# ACSN_v1.net
KiCad netlist of a schematic drawn in EAGLE
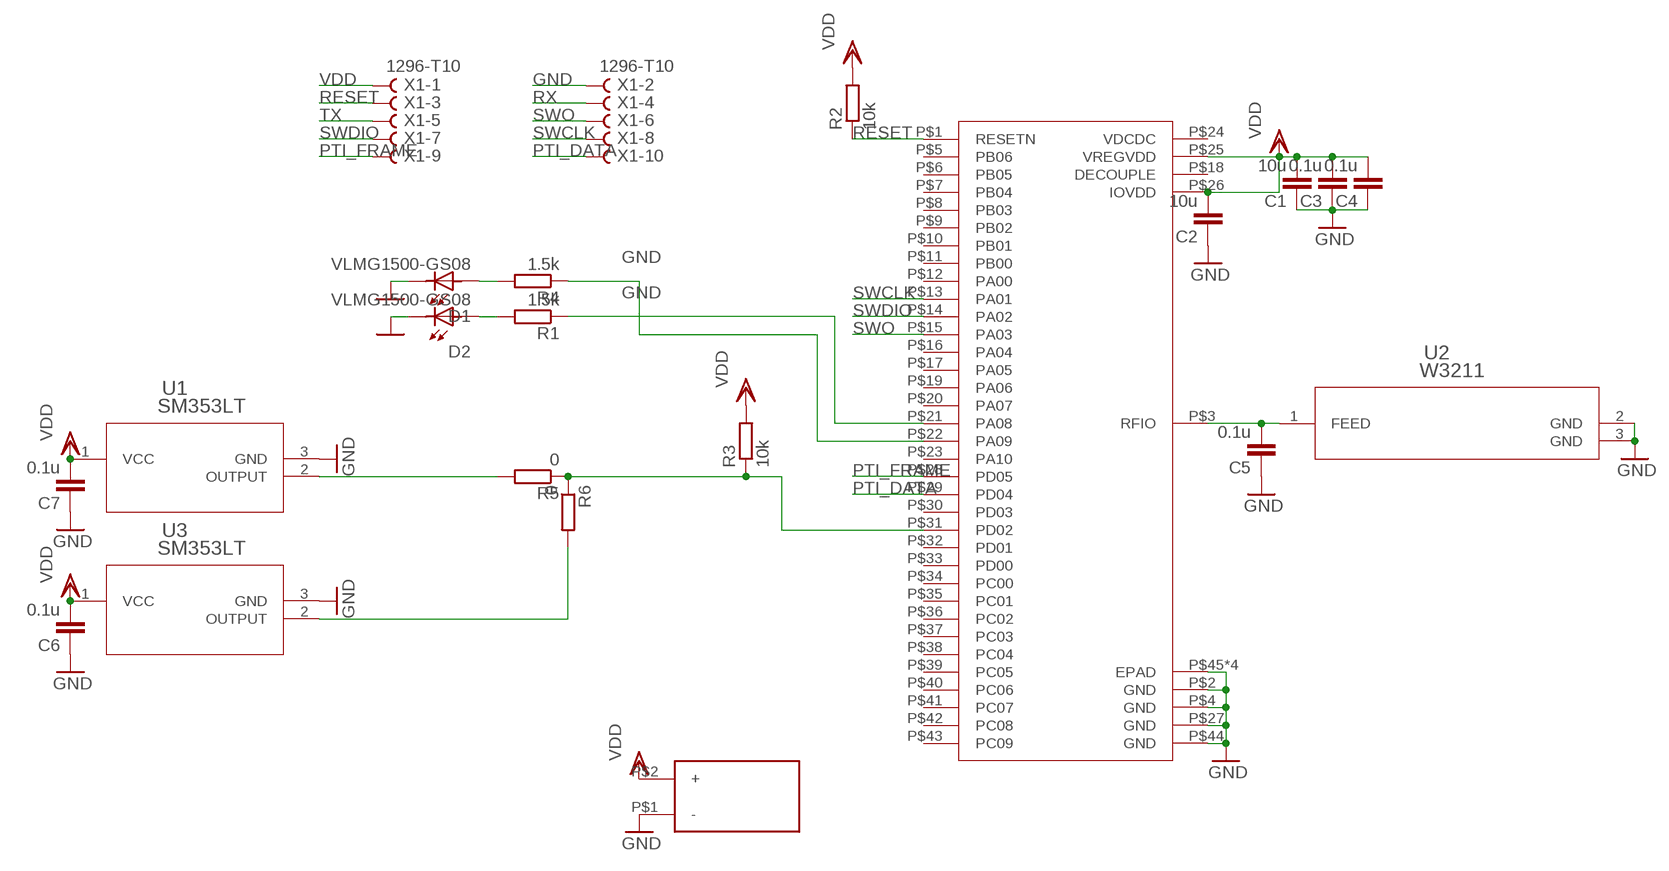
[diagram p0: schematic, sheet 1]

(export (version "E")
  (design (tool "Eeschema 10.0.6"))
  (components
    (comp (ref "C1")
      (value "10u")
      (footprint "eagle-import:C0603R")
      (libsource (lib "eagle-import") (part "CC0603R"))
    )
    (comp (ref "C2")
      (value "10u")
      (footprint "eagle-import:C0603R")
      (libsource (lib "eagle-import") (part "CC0603R"))
    )
    (comp (ref "C3")
      (value "0.1u")
      (footprint "eagle-import:C0402")
      (libsource (lib "eagle-import") (part "CC0402"))
    )
    (comp (ref "C4")
      (value "0.1u")
      (footprint "eagle-import:C0402")
      (libsource (lib "eagle-import") (part "CC0402"))
    )
    (comp (ref "C5")
      (value "0.1u")
      (footprint "eagle-import:C0402")
      (libsource (lib "eagle-import") (part "CC0402"))
    )
    (comp (ref "C6")
      (value "0.1u")
      (footprint "eagle-import:C0402")
      (libsource (lib "eagle-import") (part "CC0402"))
    )
    (comp (ref "C7")
      (value "0.1u")
      (footprint "eagle-import:C0402")
      (libsource (lib "eagle-import") (part "CC0402"))
    )
    (comp (ref "D1")
      (value "VLMG1500-GS08")
      (footprint "eagle-import:LEDC1005X35N")
      (fields (field (name "MF") "Vishay"))
      (libsource (lib "eagle-import") (part "VLMG1500-GS08"))
    )
    (comp (ref "D2")
      (value "VLMG1500-GS08")
      (footprint "eagle-import:LEDC1005X35N")
      (fields (field (name "MF") "Vishay"))
      (libsource (lib "eagle-import") (part "VLMG1500-GS08"))
    )
    (comp (ref "R1")
      (value "1.5k")
      (footprint "eagle-import:R0402")
      (libsource (lib "eagle-import") (part "RR0402"))
    )
    (comp (ref "R2")
      (value "10k")
      (footprint "eagle-import:R0402")
      (libsource (lib "eagle-import") (part "RR0402"))
    )
    (comp (ref "R3")
      (value "10k")
      (footprint "eagle-import:R0402")
      (libsource (lib "eagle-import") (part "RR0402"))
    )
    (comp (ref "R4")
      (value "1.5k")
      (footprint "eagle-import:R0402")
      (libsource (lib "eagle-import") (part "RR0402"))
    )
    (comp (ref "R5")
      (value "0")
      (footprint "eagle-import:R0402")
      (libsource (lib "eagle-import") (part "RR0402"))
    )
    (comp (ref "R6")
      (value "0")
      (footprint "eagle-import:R0402")
      (libsource (lib "eagle-import") (part "RR0402"))
    )
    (comp (ref "U$1")
      (value "ZGM230S")
      (footprint "eagle-import:ZGM230S")
      (libsource (lib "eagle-import") (part "ZGM230S"))
    )
    (comp (ref "U$2")
      (value "BS-24R")
      (footprint "eagle-import:BS-24")
      (libsource (lib "eagle-import") (part "BS-24R"))
    )
    (comp (ref "U1")
      (value "SM353LT")
      (footprint "eagle-import:SM353LT_HNW")
      (fields (field (name "COPYRIGHT") "Copyright (C) 2022 Ultra Librarian. All rights reserved."))
      (libsource (lib "eagle-import") (part "SM353LT"))
    )
    (comp (ref "U2")
      (value "W3211")
      (footprint "eagle-import:CHIP_3211_PUL")
      (fields (field (name "COPYRIGHT") "Copyright (C) 2022 Ultra Librarian. All rights reserved."))
      (libsource (lib "eagle-import") (part "W3211"))
    )
    (comp (ref "U3")
      (value "SM353LT")
      (footprint "eagle-import:SM353LT_HNW")
      (fields (field (name "COPYRIGHT") "Copyright (C) 2022 Ultra Librarian. All rights reserved."))
      (libsource (lib "eagle-import") (part "SM353LT"))
    )
    (comp (ref "X1")
      (value "1296-T10")
      (footprint "eagle-import:1296-10")
      (libsource (lib "eagle-import") (part "1296-T10"))
    )
  )
  (nets
    (net (code "1") (name "/PTI_DATA") (class "Default")
      (node (ref "U$1") (pin "P$29") (pinfunction "PD04_P$29") (pintype "bidirectional"))
      (node (ref "X1") (pin "10") (pinfunction "B_10") (pintype "passive"))
    )
    (net (code "2") (name "/PTI_FRAME") (class "Default")
      (node (ref "U$1") (pin "P$28") (pinfunction "PD05_P$28") (pintype "bidirectional"))
      (node (ref "X1") (pin "9") (pinfunction "B_9") (pintype "passive"))
    )
    (net (code "3") (name "/RESET") (class "Default")
      (node (ref "R2") (pin "1") (pinfunction "1_1") (pintype "passive"))
      (node (ref "U$1") (pin "P$1") (pinfunction "RESETN_P$1") (pintype "bidirectional"))
      (node (ref "X1") (pin "3") (pinfunction "B_3") (pintype "passive"))
    )
    (net (code "4") (name "/RX") (class "Default")
      (node (ref "X1") (pin "4") (pinfunction "B_4") (pintype "passive"))
    )
    (net (code "5") (name "/SWCLK") (class "Default")
      (node (ref "U$1") (pin "P$13") (pinfunction "PA01_P$13") (pintype "bidirectional"))
      (node (ref "X1") (pin "8") (pinfunction "B_8") (pintype "passive"))
    )
    (net (code "6") (name "/SWDIO") (class "Default")
      (node (ref "U$1") (pin "P$14") (pinfunction "PA02_P$14") (pintype "bidirectional"))
      (node (ref "X1") (pin "7") (pinfunction "B_7") (pintype "passive"))
    )
    (net (code "7") (name "/SWO") (class "Default")
      (node (ref "U$1") (pin "P$15") (pinfunction "PA03_P$15") (pintype "bidirectional"))
      (node (ref "X1") (pin "6") (pinfunction "B_6") (pintype "passive"))
    )
    (net (code "8") (name "/TX") (class "Default")
      (node (ref "X1") (pin "5") (pinfunction "B_5") (pintype "passive"))
    )
    (net (code "9") (name "GND") (class "Default")
      (node (ref "C1") (pin "1") (pinfunction "1_1") (pintype "passive"))
      (node (ref "C2") (pin "1") (pinfunction "1_1") (pintype "passive"))
      (node (ref "C3") (pin "1") (pinfunction "1_1") (pintype "passive"))
      (node (ref "C4") (pin "1") (pinfunction "1_1") (pintype "passive"))
      (node (ref "C5") (pin "1") (pinfunction "1_1") (pintype "passive"))
      (node (ref "C6") (pin "1") (pinfunction "1_1") (pintype "passive"))
      (node (ref "C7") (pin "1") (pinfunction "1_1") (pintype "passive"))
      (node (ref "D1") (pin "2") (pinfunction "2_2") (pintype "passive"))
      (node (ref "D2") (pin "2") (pinfunction "2_2") (pintype "passive"))
      (node (ref "U$1") (pin "P$2") (pinfunction "GND_P$2") (pintype "bidirectional"))
      (node (ref "U$1") (pin "P$27") (pinfunction "GND_P$27") (pintype "bidirectional"))
      (node (ref "U$1") (pin "P$4") (pinfunction "GND_P$4") (pintype "bidirectional"))
      (node (ref "U$1") (pin "P$44") (pinfunction "GND_P$44") (pintype "bidirectional"))
      (node (ref "U$1") (pin "P$45") (pinfunction "EPAD_P$45") (pintype "bidirectional"))
      (node (ref "U$1") (pin "P$46") (pinfunction "EPAD_P$46") (pintype "bidirectional"))
      (node (ref "U$1") (pin "P$47") (pinfunction "EPAD_P$47") (pintype "bidirectional"))
      (node (ref "U$1") (pin "P$48") (pinfunction "EPAD_P$48") (pintype "bidirectional"))
      (node (ref "U$2") (pin "P$1") (pinfunction "-_P$1") (pintype "bidirectional"))
      (node (ref "U1") (pin "3") (pinfunction "GND_3") (pintype "passive"))
      (node (ref "U2") (pin "2") (pinfunction "GND_2") (pintype "passive"))
      (node (ref "U2") (pin "3") (pinfunction "GND_3") (pintype "passive"))
      (node (ref "U3") (pin "3") (pinfunction "GND_3") (pintype "passive"))
      (node (ref "X1") (pin "2") (pinfunction "B_2") (pintype "passive"))
    )
    (net (code "10") (name "Net-(D1-Pad1)") (class "Default")
      (node (ref "D1") (pin "1") (pinfunction "1_1") (pintype "passive"))
      (node (ref "R4") (pin "2") (pinfunction "2_2") (pintype "passive"))
    )
    (net (code "11") (name "Net-(D2-Pad1)") (class "Default")
      (node (ref "D2") (pin "1") (pinfunction "1_1") (pintype "passive"))
      (node (ref "R1") (pin "2") (pinfunction "2_2") (pintype "passive"))
    )
    (net (code "12") (name "Net-(U$1-PA08)") (class "Default")
      (node (ref "R1") (pin "1") (pinfunction "1_1") (pintype "passive"))
      (node (ref "U$1") (pin "P$21") (pinfunction "PA08_P$21") (pintype "bidirectional"))
    )
    (net (code "13") (name "Net-(U$1-PA09)") (class "Default")
      (node (ref "R4") (pin "1") (pinfunction "1_1") (pintype "passive"))
      (node (ref "U$1") (pin "P$22") (pinfunction "PA09_P$22") (pintype "bidirectional"))
    )
    (net (code "14") (name "Net-(U$1-PD02)") (class "Default")
      (node (ref "R3") (pin "1") (pinfunction "1_1") (pintype "passive"))
      (node (ref "R5") (pin "1") (pinfunction "1_1") (pintype "passive"))
      (node (ref "R6") (pin "1") (pinfunction "1_1") (pintype "passive"))
      (node (ref "U$1") (pin "P$31") (pinfunction "PD02_P$31") (pintype "bidirectional"))
    )
    (net (code "15") (name "Net-(U$1-RFIO)") (class "Default")
      (node (ref "C5") (pin "2") (pinfunction "2_2") (pintype "passive"))
      (node (ref "U$1") (pin "P$3") (pinfunction "RFIO_P$3") (pintype "bidirectional"))
      (node (ref "U2") (pin "1") (pinfunction "FEED_1") (pintype "passive"))
    )
    (net (code "16") (name "Net-(U1-OUTPUT)") (class "Default")
      (node (ref "R5") (pin "2") (pinfunction "2_2") (pintype "passive"))
      (node (ref "U1") (pin "2") (pinfunction "OUTPUT_2") (pintype "output"))
    )
    (net (code "17") (name "Net-(U3-OUTPUT)") (class "Default")
      (node (ref "R6") (pin "2") (pinfunction "2_2") (pintype "passive"))
      (node (ref "U3") (pin "2") (pinfunction "OUTPUT_2") (pintype "output"))
    )
    (net (code "18") (name "VDD") (class "Default")
      (node (ref "C1") (pin "2") (pinfunction "2_2") (pintype "passive"))
      (node (ref "C2") (pin "2") (pinfunction "2_2") (pintype "passive"))
      (node (ref "C3") (pin "2") (pinfunction "2_2") (pintype "passive"))
      (node (ref "C4") (pin "2") (pinfunction "2_2") (pintype "passive"))
      (node (ref "C6") (pin "2") (pinfunction "2_2") (pintype "passive"))
      (node (ref "C7") (pin "2") (pinfunction "2_2") (pintype "passive"))
      (node (ref "R2") (pin "2") (pinfunction "2_2") (pintype "passive"))
      (node (ref "R3") (pin "2") (pinfunction "2_2") (pintype "passive"))
      (node (ref "U$1") (pin "P$25") (pinfunction "VREGVDD_P$25") (pintype "bidirectional"))
      (node (ref "U$1") (pin "P$26") (pinfunction "IOVDD_P$26") (pintype "bidirectional"))
      (node (ref "U$2") (pin "P$2") (pinfunction "+_P$2") (pintype "bidirectional"))
      (node (ref "U1") (pin "1") (pinfunction "VCC_1") (pintype "power_in"))
      (node (ref "U3") (pin "1") (pinfunction "VCC_1") (pintype "power_in"))
      (node (ref "X1") (pin "1") (pinfunction "B_1") (pintype "passive"))
    )
    (net (code "19") (name "unconnected-(U$1-DECOUPLE-PadP$18)") (class "Default")
      (node (ref "U$1") (pin "P$18") (pinfunction "DECOUPLE_P$18") (pintype "bidirectional"))
    )
    (net (code "20") (name "unconnected-(U$1-PA00-PadP$12)") (class "Default")
      (node (ref "U$1") (pin "P$12") (pinfunction "PA00_P$12") (pintype "bidirectional"))
    )
    (net (code "21") (name "unconnected-(U$1-PA04-PadP$16)") (class "Default")
      (node (ref "U$1") (pin "P$16") (pinfunction "PA04_P$16") (pintype "bidirectional"))
    )
    (net (code "22") (name "unconnected-(U$1-PA05-PadP$17)") (class "Default")
      (node (ref "U$1") (pin "P$17") (pinfunction "PA05_P$17") (pintype "bidirectional"))
    )
    (net (code "23") (name "unconnected-(U$1-PA06-PadP$19)") (class "Default")
      (node (ref "U$1") (pin "P$19") (pinfunction "PA06_P$19") (pintype "bidirectional"))
    )
    (net (code "24") (name "unconnected-(U$1-PA07-PadP$20)") (class "Default")
      (node (ref "U$1") (pin "P$20") (pinfunction "PA07_P$20") (pintype "bidirectional"))
    )
    (net (code "25") (name "unconnected-(U$1-PA10-PadP$23)") (class "Default")
      (node (ref "U$1") (pin "P$23") (pinfunction "PA10_P$23") (pintype "bidirectional"))
    )
    (net (code "26") (name "unconnected-(U$1-PB00-PadP$11)") (class "Default")
      (node (ref "U$1") (pin "P$11") (pinfunction "PB00_P$11") (pintype "bidirectional"))
    )
    (net (code "27") (name "unconnected-(U$1-PB01-PadP$10)") (class "Default")
      (node (ref "U$1") (pin "P$10") (pinfunction "PB01_P$10") (pintype "bidirectional"))
    )
    (net (code "28") (name "unconnected-(U$1-PB02-PadP$9)") (class "Default")
      (node (ref "U$1") (pin "P$9") (pinfunction "PB02_P$9") (pintype "bidirectional"))
    )
    (net (code "29") (name "unconnected-(U$1-PB03-PadP$8)") (class "Default")
      (node (ref "U$1") (pin "P$8") (pinfunction "PB03_P$8") (pintype "bidirectional"))
    )
    (net (code "30") (name "unconnected-(U$1-PB04-PadP$7)") (class "Default")
      (node (ref "U$1") (pin "P$7") (pinfunction "PB04_P$7") (pintype "bidirectional"))
    )
    (net (code "31") (name "unconnected-(U$1-PB05-PadP$6)") (class "Default")
      (node (ref "U$1") (pin "P$6") (pinfunction "PB05_P$6") (pintype "bidirectional"))
    )
    (net (code "32") (name "unconnected-(U$1-PB06-PadP$5)") (class "Default")
      (node (ref "U$1") (pin "P$5") (pinfunction "PB06_P$5") (pintype "bidirectional"))
    )
    (net (code "33") (name "unconnected-(U$1-PC00-PadP$34)") (class "Default")
      (node (ref "U$1") (pin "P$34") (pinfunction "PC00_P$34") (pintype "bidirectional"))
    )
    (net (code "34") (name "unconnected-(U$1-PC01-PadP$35)") (class "Default")
      (node (ref "U$1") (pin "P$35") (pinfunction "PC01_P$35") (pintype "bidirectional"))
    )
    (net (code "35") (name "unconnected-(U$1-PC02-PadP$36)") (class "Default")
      (node (ref "U$1") (pin "P$36") (pinfunction "PC02_P$36") (pintype "bidirectional"))
    )
    (net (code "36") (name "unconnected-(U$1-PC03-PadP$37)") (class "Default")
      (node (ref "U$1") (pin "P$37") (pinfunction "PC03_P$37") (pintype "bidirectional"))
    )
    (net (code "37") (name "unconnected-(U$1-PC04-PadP$38)") (class "Default")
      (node (ref "U$1") (pin "P$38") (pinfunction "PC04_P$38") (pintype "bidirectional"))
    )
    (net (code "38") (name "unconnected-(U$1-PC05-PadP$39)") (class "Default")
      (node (ref "U$1") (pin "P$39") (pinfunction "PC05_P$39") (pintype "bidirectional"))
    )
    (net (code "39") (name "unconnected-(U$1-PC06-PadP$40)") (class "Default")
      (node (ref "U$1") (pin "P$40") (pinfunction "PC06_P$40") (pintype "bidirectional"))
    )
    (net (code "40") (name "unconnected-(U$1-PC07-PadP$41)") (class "Default")
      (node (ref "U$1") (pin "P$41") (pinfunction "PC07_P$41") (pintype "bidirectional"))
    )
    (net (code "41") (name "unconnected-(U$1-PC08-PadP$42)") (class "Default")
      (node (ref "U$1") (pin "P$42") (pinfunction "PC08_P$42") (pintype "bidirectional"))
    )
    (net (code "42") (name "unconnected-(U$1-PC09-PadP$43)") (class "Default")
      (node (ref "U$1") (pin "P$43") (pinfunction "PC09_P$43") (pintype "bidirectional"))
    )
    (net (code "43") (name "unconnected-(U$1-PD00-PadP$33)") (class "Default")
      (node (ref "U$1") (pin "P$33") (pinfunction "PD00_P$33") (pintype "bidirectional"))
    )
    (net (code "44") (name "unconnected-(U$1-PD01-PadP$32)") (class "Default")
      (node (ref "U$1") (pin "P$32") (pinfunction "PD01_P$32") (pintype "bidirectional"))
    )
    (net (code "45") (name "unconnected-(U$1-PD03-PadP$30)") (class "Default")
      (node (ref "U$1") (pin "P$30") (pinfunction "PD03_P$30") (pintype "bidirectional"))
    )
    (net (code "46") (name "unconnected-(U$1-VDCDC-PadP$24)") (class "Default")
      (node (ref "U$1") (pin "P$24") (pinfunction "VDCDC_P$24") (pintype "bidirectional"))
    )
  )
)
